# GasSensor.net
KiCad netlist of a schematic drawn in EAGLE
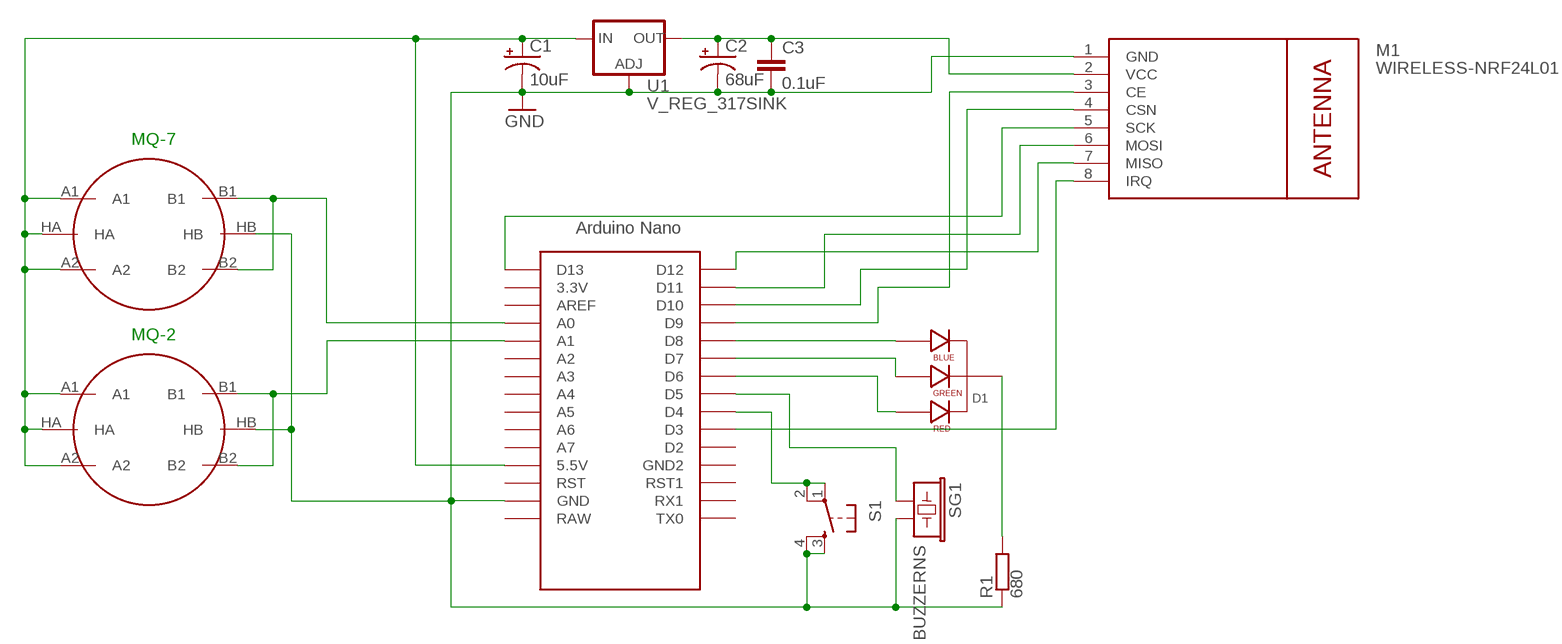
[diagram p0: schematic, sheet 1]

(export (version "E")
  (design (tool "Eeschema 10.0.6"))
  (components
    (comp (ref "C1")
      (value "10uF")
      (footprint "eagle-import:EIA3216")
      (libsource (lib "eagle-import") (part "CAP_POL1206"))
    )
    (comp (ref "C2")
      (value "68uF")
      (footprint "eagle-import:EIA3216")
      (libsource (lib "eagle-import") (part "CAP_POL1206"))
    )
    (comp (ref "C3")
      (value "0.1uF")
      (footprint "eagle-import:CAP-PTH-SMALLEZ")
      (libsource (lib "eagle-import") (part "CAPEZ"))
    )
    (comp (ref "D1")
      (value "LED-RGB-CC-THRUCLEAR")
      (footprint "eagle-import:LED-RGB-THRU")
      (libsource (lib "eagle-import") (part "LED-RGB-CC-THRUCLEAR"))
    )
    (comp (ref "M1")
      (value "WIRELESS-NRF24L01")
      (footprint "eagle-import:WIRELESS-NRF24L01")
      (libsource (lib "eagle-import") (part "WIRELESS-NRF24L01"))
    )
    (comp (ref "R1")
      (value "680")
      (footprint "eagle-import:SMK")
      (libsource (lib "eagle-import") (part "SMK"))
    )
    (comp (ref "S1")
      (value "TAC_SWITCHPTH")
      (footprint "eagle-import:TACTILE-PTH")
      (libsource (lib "eagle-import") (part "TAC_SWITCHPTH"))
    )
    (comp (ref "SG1")
      (value "BUZZERNS")
      (footprint "eagle-import:BUZZER-12MM-NS")
      (libsource (lib "eagle-import") (part "BUZZERNS"))
    )
    (comp (ref "U$1")
      (value "NANO")
      (footprint "eagle-import:NANO")
      (libsource (lib "eagle-import") (part "NANO"))
    )
    (comp (ref "U$2")
      (value "CO2_SENSOR")
      (footprint "eagle-import:MQ-3")
      (libsource (lib "eagle-import") (part "METHANE_SENSOR"))
    )
    (comp (ref "U$3")
      (value "METHANE_SENSOR")
      (footprint "eagle-import:MQ-3")
      (libsource (lib "eagle-import") (part "METHANE_SENSOR"))
    )
    (comp (ref "U1")
      (value "V_REG_317SINK")
      (footprint "eagle-import:TO220-ADJ")
      (libsource (lib "eagle-import") (part "V_REG_317SINK"))
    )
  )
  (nets
    (net (code "1") (name "GND") (class "Default")
      (node (ref "C1") (pin "C") (pinfunction "-_C") (pintype "passive"))
      (node (ref "C2") (pin "C") (pinfunction "-_C") (pintype "passive"))
      (node (ref "C3") (pin "2") (pinfunction "2_2") (pintype "passive"))
      (node (ref "M1") (pin "1") (pinfunction "GND_1") (pintype "power_in"))
      (node (ref "R1") (pin "2") (pinfunction "2_2") (pintype "passive"))
      (node (ref "S1") (pin "3") (pinfunction "3_3") (pintype "passive"))
      (node (ref "S1") (pin "4") (pinfunction "4_4") (pintype "passive"))
      (node (ref "SG1") (pin "-") (pinfunction "2_-") (pintype "passive"))
      (node (ref "U$1") (pin "GND") (pinfunction "GND_GND") (pintype "bidirectional"))
      (node (ref "U$2") (pin "HB") (pinfunction "HB_HB") (pintype "bidirectional"))
      (node (ref "U$3") (pin "HB") (pinfunction "HB_HB") (pintype "bidirectional"))
      (node (ref "U1") (pin "ADJ") (pinfunction "ADJ_ADJ") (pintype "input"))
    )
    (net (code "2") (name "Net-(C1-+)") (class "Default")
      (node (ref "C1") (pin "A") (pinfunction "+_A") (pintype "passive"))
      (node (ref "U$1") (pin "5V") (pinfunction "5.5V_5V") (pintype "bidirectional"))
      (node (ref "U$2") (pin "A1") (pinfunction "A1_A1") (pintype "bidirectional"))
      (node (ref "U$2") (pin "A2") (pinfunction "A2_A2") (pintype "bidirectional"))
      (node (ref "U$2") (pin "HA") (pinfunction "HA_HA") (pintype "bidirectional"))
      (node (ref "U$3") (pin "A1") (pinfunction "A1_A1") (pintype "bidirectional"))
      (node (ref "U$3") (pin "A2") (pinfunction "A2_A2") (pintype "bidirectional"))
      (node (ref "U$3") (pin "HA") (pinfunction "HA_HA") (pintype "bidirectional"))
      (node (ref "U1") (pin "IN") (pinfunction "IN_IN") (pintype "input"))
    )
    (net (code "3") (name "Net-(C2-+)") (class "Default")
      (node (ref "C2") (pin "A") (pinfunction "+_A") (pintype "passive"))
      (node (ref "C3") (pin "1") (pinfunction "1_1") (pintype "passive"))
      (node (ref "M1") (pin "2") (pinfunction "VCC_2") (pintype "power_in"))
      (node (ref "U1") (pin "OUT") (pinfunction "OUT_OUT") (pintype "output"))
    )
    (net (code "4") (name "Net-(D1-BLUE_CATHODE)") (class "Default")
      (node (ref "D1") (pin "4") (pinfunction "BLUE_CATHODE_4") (pintype "bidirectional"))
      (node (ref "U$1") (pin "D8") (pinfunction "D8_D8") (pintype "bidirectional"))
    )
    (net (code "5") (name "Net-(D1-CATHODE)") (class "Default")
      (node (ref "D1") (pin "2") (pinfunction "CATHODE_2") (pintype "bidirectional"))
      (node (ref "R1") (pin "1") (pinfunction "1_1") (pintype "passive"))
    )
    (net (code "6") (name "Net-(D1-GREEN_CATHODE)") (class "Default")
      (node (ref "D1") (pin "3") (pinfunction "GREEN_CATHODE_3") (pintype "bidirectional"))
      (node (ref "U$1") (pin "D7") (pinfunction "D7_D7") (pintype "bidirectional"))
    )
    (net (code "7") (name "Net-(D1-RED_CATHODE)") (class "Default")
      (node (ref "D1") (pin "1") (pinfunction "RED_CATHODE_1") (pintype "bidirectional"))
      (node (ref "U$1") (pin "D6") (pinfunction "D6_D6") (pintype "bidirectional"))
    )
    (net (code "8") (name "Net-(M1-CE)") (class "Default")
      (node (ref "M1") (pin "3") (pinfunction "CE_3") (pintype "bidirectional"))
      (node (ref "U$1") (pin "D9") (pinfunction "D9_D9") (pintype "bidirectional"))
    )
    (net (code "9") (name "Net-(M1-CSN)") (class "Default")
      (node (ref "M1") (pin "4") (pinfunction "CSN_4") (pintype "bidirectional"))
      (node (ref "U$1") (pin "D10") (pinfunction "D10_D10") (pintype "bidirectional"))
    )
    (net (code "10") (name "Net-(M1-IRQ)") (class "Default")
      (node (ref "M1") (pin "8") (pinfunction "IRQ_8") (pintype "bidirectional"))
      (node (ref "U$1") (pin "D3") (pinfunction "D3_D3") (pintype "bidirectional"))
    )
    (net (code "11") (name "Net-(M1-MISO)") (class "Default")
      (node (ref "M1") (pin "7") (pinfunction "MISO_7") (pintype "bidirectional"))
      (node (ref "U$1") (pin "D12") (pinfunction "D12_D12") (pintype "bidirectional"))
    )
    (net (code "12") (name "Net-(M1-MOSI)") (class "Default")
      (node (ref "M1") (pin "6") (pinfunction "MOSI_6") (pintype "bidirectional"))
      (node (ref "U$1") (pin "D11") (pinfunction "D11_D11") (pintype "bidirectional"))
    )
    (net (code "13") (name "Net-(M1-SCK)") (class "Default")
      (node (ref "M1") (pin "5") (pinfunction "SCK_5") (pintype "bidirectional"))
      (node (ref "U$1") (pin "D13") (pinfunction "D13_D13") (pintype "bidirectional"))
    )
    (net (code "14") (name "Net-(S1-Pad1)") (class "Default")
      (node (ref "S1") (pin "1") (pinfunction "1_1") (pintype "passive"))
      (node (ref "S1") (pin "2") (pinfunction "2_2") (pintype "passive"))
      (node (ref "U$1") (pin "D4") (pinfunction "D4_D4") (pintype "bidirectional"))
    )
    (net (code "15") (name "Net-(SG1-1)") (class "Default")
      (node (ref "SG1") (pin "+") (pinfunction "1_+") (pintype "passive"))
      (node (ref "U$1") (pin "D5") (pinfunction "D5_D5") (pintype "bidirectional"))
    )
    (net (code "16") (name "Net-(U$1-PadA0)") (class "Default")
      (node (ref "U$1") (pin "A0") (pinfunction "A0_A0") (pintype "bidirectional"))
      (node (ref "U$2") (pin "B1") (pinfunction "B1_B1") (pintype "bidirectional"))
      (node (ref "U$2") (pin "B2") (pinfunction "B2_B2") (pintype "bidirectional"))
    )
    (net (code "17") (name "Net-(U$1-PadA1)") (class "Default")
      (node (ref "U$1") (pin "A1") (pinfunction "A1_A1") (pintype "bidirectional"))
      (node (ref "U$3") (pin "B1") (pinfunction "B1_B1") (pintype "bidirectional"))
      (node (ref "U$3") (pin "B2") (pinfunction "B2_B2") (pintype "bidirectional"))
    )
    (net (code "18") (name "unconnected-(U$1-GND2-PadGND1)") (class "Default")
      (node (ref "U$1") (pin "GND1") (pinfunction "GND2_GND1") (pintype "bidirectional"))
    )
    (net (code "19") (name "unconnected-(U$1-Pad3.3V)") (class "Default")
      (node (ref "U$1") (pin "3.3V") (pinfunction "3.3V_3.3V") (pintype "bidirectional"))
    )
    (net (code "20") (name "unconnected-(U$1-PadA2)") (class "Default")
      (node (ref "U$1") (pin "A2") (pinfunction "A2_A2") (pintype "bidirectional"))
    )
    (net (code "21") (name "unconnected-(U$1-PadA3)") (class "Default")
      (node (ref "U$1") (pin "A3") (pinfunction "A3_A3") (pintype "bidirectional"))
    )
    (net (code "22") (name "unconnected-(U$1-PadA4)") (class "Default")
      (node (ref "U$1") (pin "A4") (pinfunction "A4_A4") (pintype "bidirectional"))
    )
    (net (code "23") (name "unconnected-(U$1-PadA5)") (class "Default")
      (node (ref "U$1") (pin "A5") (pinfunction "A5_A5") (pintype "bidirectional"))
    )
    (net (code "24") (name "unconnected-(U$1-PadA6)") (class "Default")
      (node (ref "U$1") (pin "A6") (pinfunction "A6_A6") (pintype "bidirectional"))
    )
    (net (code "25") (name "unconnected-(U$1-PadA7)") (class "Default")
      (node (ref "U$1") (pin "A7") (pinfunction "A7_A7") (pintype "bidirectional"))
    )
    (net (code "26") (name "unconnected-(U$1-PadAREF)") (class "Default")
      (node (ref "U$1") (pin "AREF") (pinfunction "AREF_AREF") (pintype "bidirectional"))
    )
    (net (code "27") (name "unconnected-(U$1-PadD2)") (class "Default")
      (node (ref "U$1") (pin "D2") (pinfunction "D2_D2") (pintype "bidirectional"))
    )
    (net (code "28") (name "unconnected-(U$1-PadICSP1)") (class "Default")
      (node (ref "U$1") (pin "ICSP1") (pinfunction "ICSP1_ICSP1") (pintype "bidirectional"))
    )
    (net (code "29") (name "unconnected-(U$1-PadICSP2)") (class "Default")
      (node (ref "U$1") (pin "ICSP2") (pinfunction "ICSP2_ICSP2") (pintype "bidirectional"))
    )
    (net (code "30") (name "unconnected-(U$1-PadICSP3)") (class "Default")
      (node (ref "U$1") (pin "ICSP3") (pinfunction "ICSP3_ICSP3") (pintype "bidirectional"))
    )
    (net (code "31") (name "unconnected-(U$1-PadICSP4)") (class "Default")
      (node (ref "U$1") (pin "ICSP4") (pinfunction "ICSP4_ICSP4") (pintype "bidirectional"))
    )
    (net (code "32") (name "unconnected-(U$1-PadICSP5)") (class "Default")
      (node (ref "U$1") (pin "ICSP5") (pinfunction "ICSP5_ICSP5") (pintype "bidirectional"))
    )
    (net (code "33") (name "unconnected-(U$1-PadICSP6)") (class "Default")
      (node (ref "U$1") (pin "ICSP6") (pinfunction "ICSP6_ICSP6") (pintype "bidirectional"))
    )
    (net (code "34") (name "unconnected-(U$1-PadRAW)") (class "Default")
      (node (ref "U$1") (pin "RAW") (pinfunction "RAW_RAW") (pintype "bidirectional"))
    )
    (net (code "35") (name "unconnected-(U$1-PadRST)") (class "Default")
      (node (ref "U$1") (pin "RST") (pinfunction "RST_RST") (pintype "bidirectional"))
    )
    (net (code "36") (name "unconnected-(U$1-PadRST1)") (class "Default")
      (node (ref "U$1") (pin "RST1") (pinfunction "RST1_RST1") (pintype "bidirectional"))
    )
    (net (code "37") (name "unconnected-(U$1-PadRX1)") (class "Default")
      (node (ref "U$1") (pin "RX1") (pinfunction "RX1_RX1") (pintype "bidirectional"))
    )
    (net (code "38") (name "unconnected-(U$1-PadTX0)") (class "Default")
      (node (ref "U$1") (pin "TX0") (pinfunction "TX0_TX0") (pintype "bidirectional"))
    )
  )
)
